# ProProject__20240517_2024-08-10.net
KiCad netlist of a schematic drawn in EasyEDA Pro
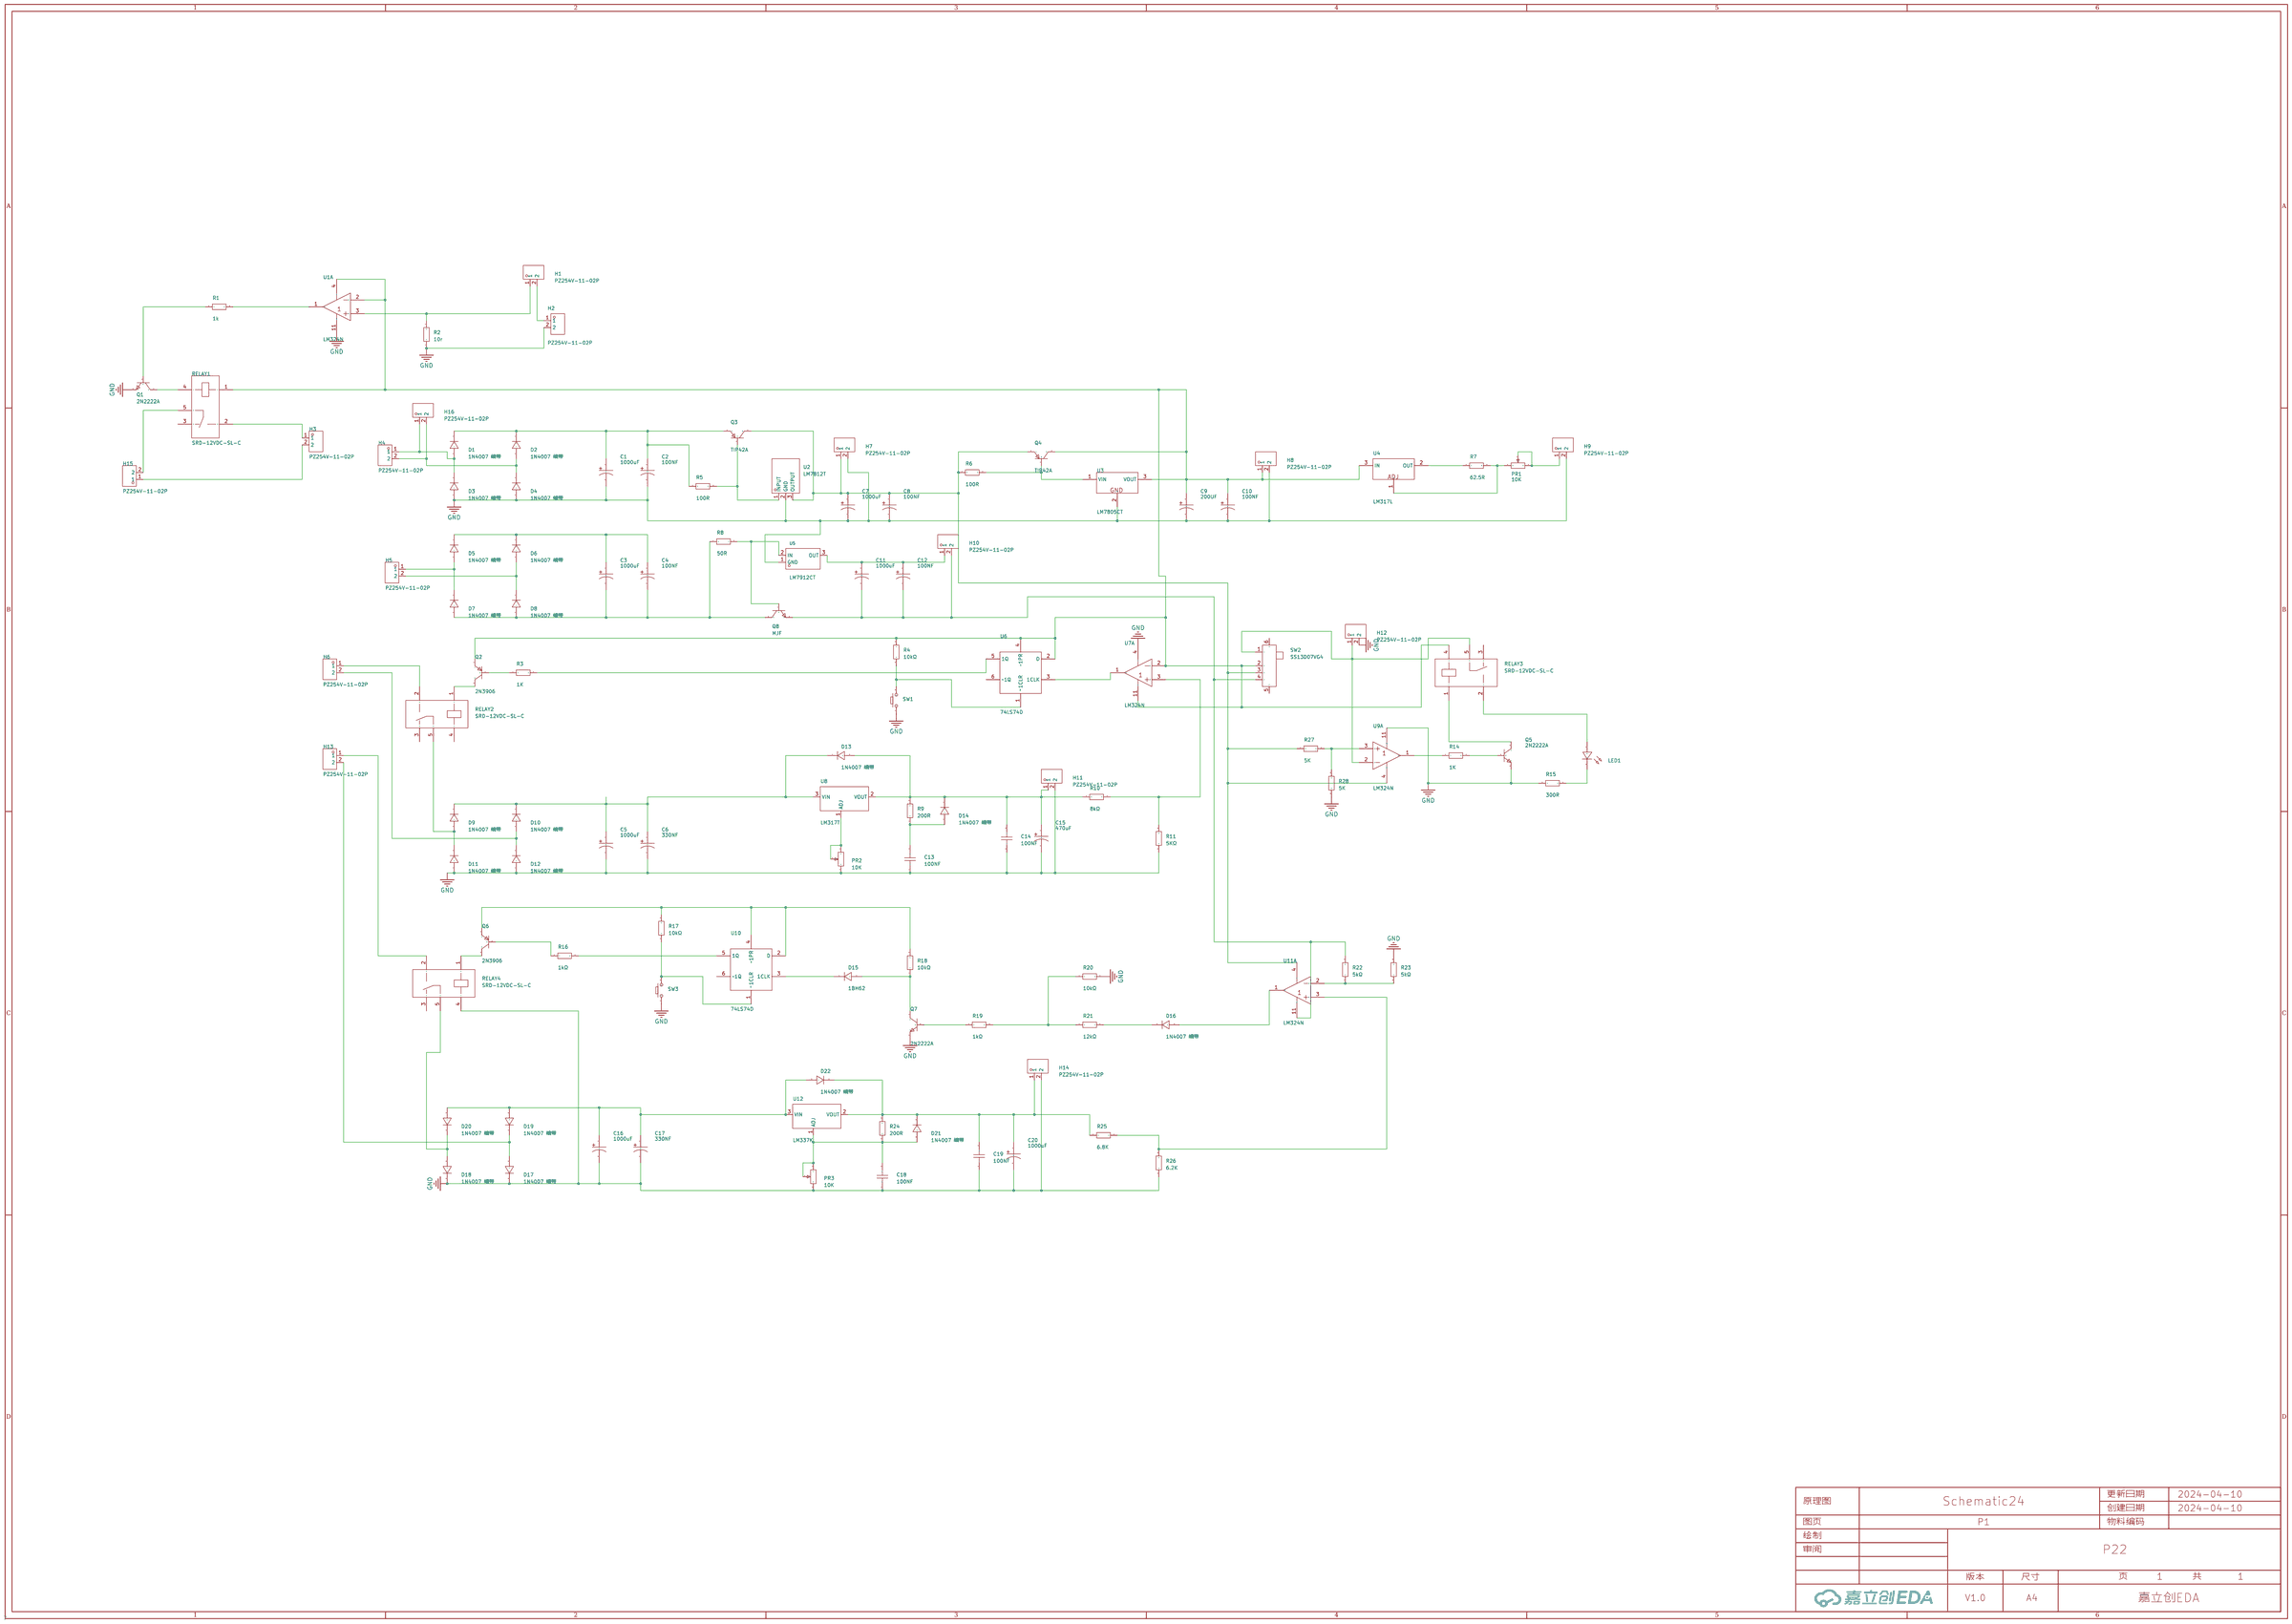
[diagram p0: schematic sheet]

(export (version "E")
  (design (tool "Eeschema 10.0.6"))
  (components
    (comp (ref "C1")
      (value "1000uF")
      (footprint "easyedapro:CAP-TH_BD12.5-P5.00-D0.6-FD")
      (description "容值:1000uF;精度:±20%;额定电压:35V;")
      (fields
        (field (name "Manufacturer Part") "ECLJ1321102M035P00")
        (field (name "Manufacturer") "TOPAZ(黄宝石)")
      )
      (libsource (lib "easyedapro") (part "ECLJ1321102M035P00"))
    )
    (comp (ref "C2")
      (value "100NF")
      (footprint "easyedapro:CAP-TH_BD12.5-P5.00-D0.6-FD")
      (description "容值:1000uF;精度:±20%;额定电压:35V;")
      (fields
        (field (name "Manufacturer Part") "ECLJ1321102M035P00")
        (field (name "Manufacturer") "TOPAZ(黄宝石)")
      )
      (libsource (lib "easyedapro") (part "ECLJ1321102M035P00"))
    )
    (comp (ref "C3")
      (value "1000uF")
      (footprint "easyedapro:CAP-TH_BD12.5-P5.00-D0.6-FD")
      (description "容值:1000uF;精度:±20%;额定电压:35V;")
      (fields
        (field (name "Manufacturer Part") "ECLJ1321102M035P00")
        (field (name "Manufacturer") "TOPAZ(黄宝石)")
      )
      (libsource (lib "easyedapro") (part "ECLJ1321102M035P00"))
    )
    (comp (ref "C4")
      (value "1000uF")
      (footprint "easyedapro:CAP-TH_BD12.5-P5.00-D0.6-FD")
      (description "容值:1000uF;精度:±20%;额定电压:35V;")
      (fields
        (field (name "Manufacturer Part") "ECLJ1321102M035P00")
        (field (name "Manufacturer") "TOPAZ(黄宝石)")
      )
      (libsource (lib "easyedapro") (part "ECLJ1321102M035P00"))
    )
    (comp (ref "C5")
      (value "1000uF")
      (footprint "easyedapro:CAP-TH_BD12.5-P5.00-D0.6-FD")
      (description "容值:1000uF;精度:±20%;额定电压:35V;")
      (fields
        (field (name "Manufacturer Part") "ECLJ1321102M035P00")
        (field (name "Manufacturer") "TOPAZ(黄宝石)")
      )
      (libsource (lib "easyedapro") (part "ECLJ1321102M035P00"))
    )
    (comp (ref "C6")
      (value "330NF")
      (footprint "easyedapro:CAP-TH_BD12.5-P5.00-D0.6-FD")
      (description "容值:1000uF;精度:±20%;额定电压:35V;")
      (fields
        (field (name "Manufacturer Part") "ECLJ1321102M035P00")
        (field (name "Manufacturer") "TOPAZ(黄宝石)")
      )
      (libsource (lib "easyedapro") (part "ECLJ1321102M035P00"))
    )
    (comp (ref "C7")
      (value "1000uF")
      (footprint "easyedapro:CAP-TH_BD12.5-P5.00-D0.6-FD")
      (description "容值:1000uF;精度:±20%;额定电压:35V;")
      (fields
        (field (name "Manufacturer Part") "ECLJ1321102M035P00")
        (field (name "Manufacturer") "TOPAZ(黄宝石)")
      )
      (libsource (lib "easyedapro") (part "ECLJ1321102M035P00"))
    )
    (comp (ref "C8")
      (value "100NF")
      (footprint "easyedapro:CAP-TH_BD12.5-P5.00-D0.6-FD")
      (description "容值:1000uF;精度:±20%;额定电压:35V;")
      (fields
        (field (name "Manufacturer Part") "ECLJ1321102M035P00")
        (field (name "Manufacturer") "TOPAZ(黄宝石)")
      )
      (libsource (lib "easyedapro") (part "ECLJ1321102M035P00"))
    )
    (comp (ref "C9")
      (value "200UF")
      (footprint "easyedapro:CAP-TH_BD12.5-P5.00-D0.6-FD")
      (description "容值:1000uF;精度:±20%;额定电压:35V;")
      (fields
        (field (name "Manufacturer Part") "ECLJ1321102M035P00")
        (field (name "Manufacturer") "TOPAZ(黄宝石)")
      )
      (libsource (lib "easyedapro") (part "ECLJ1321102M035P00"))
    )
    (comp (ref "C10")
      (value "100NF")
      (footprint "easyedapro:CAP-TH_BD12.5-P5.00-D0.6-FD")
      (description "容值:1000uF;精度:±20%;额定电压:35V;")
      (fields
        (field (name "Manufacturer Part") "ECLJ1321102M035P00")
        (field (name "Manufacturer") "TOPAZ(黄宝石)")
      )
      (libsource (lib "easyedapro") (part "ECLJ1321102M035P00"))
    )
    (comp (ref "C11")
      (value "1000uF")
      (footprint "easyedapro:CAP-TH_BD12.5-P5.00-D0.6-FD")
      (description "容值:1000uF;精度:±20%;额定电压:35V;")
      (fields
        (field (name "Manufacturer Part") "ECLJ1321102M035P00")
        (field (name "Manufacturer") "TOPAZ(黄宝石)")
      )
      (libsource (lib "easyedapro") (part "ECLJ1321102M035P00"))
    )
    (comp (ref "C12")
      (value "100NF")
      (footprint "easyedapro:CAP-TH_BD12.5-P5.00-D0.6-FD")
      (description "容值:1000uF;精度:±20%;额定电压:35V;")
      (fields
        (field (name "Manufacturer Part") "ECLJ1321102M035P00")
        (field (name "Manufacturer") "TOPAZ(黄宝石)")
      )
      (libsource (lib "easyedapro") (part "ECLJ1321102M035P00"))
    )
    (comp (ref "C13")
      (value "100NF")
      (footprint "easyedapro:CAP-TH_L5.5-W4.0-P5.00-D0.5")
      (description "容值:1nF;精度:±10%;额定电压:2kV;温度系数:SL;")
      (fields
        (field (name "Manufacturer Part") "Y5P102K2KV16CC0224")
        (field (name "Manufacturer") "KNSCHA(科尼盛)")
      )
      (libsource (lib "easyedapro") (part "Y5P102K2KV16CC0224"))
    )
    (comp (ref "C14")
      (value "100NF")
      (footprint "easyedapro:CAP-TH_L5.5-W4.0-P5.00-D0.5")
      (description "容值:1nF;精度:±10%;额定电压:2kV;温度系数:SL;")
      (fields
        (field (name "Manufacturer Part") "Y5P102K2KV16CC0224")
        (field (name "Manufacturer") "KNSCHA(科尼盛)")
      )
      (libsource (lib "easyedapro") (part "Y5P102K2KV16CC0224"))
    )
    (comp (ref "C15")
      (value "470uF")
      (footprint "easyedapro:CAP-TH_BD12.5-P5.00-D0.6-FD")
      (description "容值:1000uF;精度:±20%;额定电压:35V;")
      (fields
        (field (name "Manufacturer Part") "ECLJ1321102M035P00")
        (field (name "Manufacturer") "TOPAZ(黄宝石)")
      )
      (libsource (lib "easyedapro") (part "ECLJ1321102M035P00"))
    )
    (comp (ref "C16")
      (value "1000uF")
      (footprint "easyedapro:CAP-TH_BD12.5-P5.00-D0.6-FD")
      (description "容值:1000uF;精度:±20%;额定电压:35V;")
      (fields
        (field (name "Manufacturer Part") "ECLJ1321102M035P00")
        (field (name "Manufacturer") "TOPAZ(黄宝石)")
      )
      (libsource (lib "easyedapro") (part "ECLJ1321102M035P00"))
    )
    (comp (ref "C17")
      (value "330NF")
      (footprint "easyedapro:CAP-TH_BD12.5-P5.00-D0.6-FD")
      (description "容值:1000uF;精度:±20%;额定电压:35V;")
      (fields
        (field (name "Manufacturer Part") "ECLJ1321102M035P00")
        (field (name "Manufacturer") "TOPAZ(黄宝石)")
      )
      (libsource (lib "easyedapro") (part "ECLJ1321102M035P00"))
    )
    (comp (ref "C18")
      (value "100NF")
      (footprint "easyedapro:CAP-TH_L5.5-W4.0-P5.00-D0.5")
      (description "容值:1nF;精度:±10%;额定电压:2kV;温度系数:SL;")
      (fields
        (field (name "Manufacturer Part") "Y5P102K2KV16CC0224")
        (field (name "Manufacturer") "KNSCHA(科尼盛)")
      )
      (libsource (lib "easyedapro") (part "Y5P102K2KV16CC0224"))
    )
    (comp (ref "C19")
      (value "100NF")
      (footprint "easyedapro:CAP-TH_L5.5-W4.0-P5.00-D0.5")
      (description "容值:1nF;精度:±10%;额定电压:2kV;温度系数:SL;")
      (fields
        (field (name "Manufacturer Part") "Y5P102K2KV16CC0224")
        (field (name "Manufacturer") "KNSCHA(科尼盛)")
      )
      (libsource (lib "easyedapro") (part "Y5P102K2KV16CC0224"))
    )
    (comp (ref "C20")
      (value "1000uF")
      (footprint "easyedapro:CAP-TH_BD12.5-P5.00-D0.6-FD")
      (description "容值:1000uF;精度:±20%;额定电压:35V;")
      (fields
        (field (name "Manufacturer Part") "ECLJ1321102M035P00")
        (field (name "Manufacturer") "TOPAZ(黄宝石)")
      )
      (libsource (lib "easyedapro") (part "ECLJ1321102M035P00"))
    )
    (comp (ref "D1")
      (value "1N4007 编带")
      (footprint "easyedapro:DO-41_BD2.4-L4.7-P8.70-D0.9-RD")
      (description "二极管配置:-;正向压降(Vf):1.1V@1A;直流反向耐压(Vr):1kV;平均整流电流(Io):1A;")
      (fields (field (name "Manufacturer") "MDD"))
      (libsource (lib "easyedapro") (part "1N4007 Tube"))
    )
    (comp (ref "D2")
      (value "1N4007 编带")
      (footprint "easyedapro:DO-41_BD2.4-L4.7-P8.70-D0.9-RD")
      (description "二极管配置:-;正向压降(Vf):1.1V@1A;直流反向耐压(Vr):1kV;平均整流电流(Io):1A;")
      (fields (field (name "Manufacturer") "MDD"))
      (libsource (lib "easyedapro") (part "1N4007 Tube"))
    )
    (comp (ref "D3")
      (value "1N4007 编带")
      (footprint "easyedapro:DO-41_BD2.4-L4.7-P8.70-D0.9-RD")
      (description "二极管配置:-;正向压降(Vf):1.1V@1A;直流反向耐压(Vr):1kV;平均整流电流(Io):1A;")
      (fields (field (name "Manufacturer") "MDD"))
      (libsource (lib "easyedapro") (part "1N4007 Tube"))
    )
    (comp (ref "D4")
      (value "1N4007 编带")
      (footprint "easyedapro:DO-41_BD2.4-L4.7-P8.70-D0.9-RD")
      (description "二极管配置:-;正向压降(Vf):1.1V@1A;直流反向耐压(Vr):1kV;平均整流电流(Io):1A;")
      (fields (field (name "Manufacturer") "MDD"))
      (libsource (lib "easyedapro") (part "1N4007 Tube"))
    )
    (comp (ref "D5")
      (value "1N4007 编带")
      (footprint "easyedapro:DO-41_BD2.4-L4.7-P8.70-D0.9-RD")
      (description "二极管配置:-;正向压降(Vf):1.1V@1A;直流反向耐压(Vr):1kV;平均整流电流(Io):1A;")
      (fields (field (name "Manufacturer") "MDD"))
      (libsource (lib "easyedapro") (part "1N4007 Tube"))
    )
    (comp (ref "D6")
      (value "1N4007 编带")
      (footprint "easyedapro:DO-41_BD2.4-L4.7-P8.70-D0.9-RD")
      (description "二极管配置:-;正向压降(Vf):1.1V@1A;直流反向耐压(Vr):1kV;平均整流电流(Io):1A;")
      (fields (field (name "Manufacturer") "MDD"))
      (libsource (lib "easyedapro") (part "1N4007 Tube"))
    )
    (comp (ref "D7")
      (value "1N4007 编带")
      (footprint "easyedapro:DO-41_BD2.4-L4.7-P8.70-D0.9-RD")
      (description "二极管配置:-;正向压降(Vf):1.1V@1A;直流反向耐压(Vr):1kV;平均整流电流(Io):1A;")
      (fields (field (name "Manufacturer") "MDD"))
      (libsource (lib "easyedapro") (part "1N4007 Tube"))
    )
    (comp (ref "D8")
      (value "1N4007 编带")
      (footprint "easyedapro:DO-41_BD2.4-L4.7-P8.70-D0.9-RD")
      (description "二极管配置:-;正向压降(Vf):1.1V@1A;直流反向耐压(Vr):1kV;平均整流电流(Io):1A;")
      (fields (field (name "Manufacturer") "MDD"))
      (libsource (lib "easyedapro") (part "1N4007 Tube"))
    )
    (comp (ref "D9")
      (value "1N4007 编带")
      (footprint "easyedapro:DO-41_BD2.4-L4.7-P8.70-D0.9-RD")
      (description "二极管配置:-;正向压降(Vf):1.1V@1A;直流反向耐压(Vr):1kV;平均整流电流(Io):1A;")
      (fields (field (name "Manufacturer") "MDD"))
      (libsource (lib "easyedapro") (part "1N4007 Tube"))
    )
    (comp (ref "D10")
      (value "1N4007 编带")
      (footprint "easyedapro:DO-41_BD2.4-L4.7-P8.70-D0.9-RD")
      (description "二极管配置:-;正向压降(Vf):1.1V@1A;直流反向耐压(Vr):1kV;平均整流电流(Io):1A;")
      (fields (field (name "Manufacturer") "MDD"))
      (libsource (lib "easyedapro") (part "1N4007 Tube"))
    )
    (comp (ref "D11")
      (value "1N4007 编带")
      (footprint "easyedapro:DO-41_BD2.4-L4.7-P8.70-D0.9-RD")
      (description "二极管配置:-;正向压降(Vf):1.1V@1A;直流反向耐压(Vr):1kV;平均整流电流(Io):1A;")
      (fields (field (name "Manufacturer") "MDD"))
      (libsource (lib "easyedapro") (part "1N4007 Tube"))
    )
    (comp (ref "D12")
      (value "1N4007 编带")
      (footprint "easyedapro:DO-41_BD2.4-L4.7-P8.70-D0.9-RD")
      (description "二极管配置:-;正向压降(Vf):1.1V@1A;直流反向耐压(Vr):1kV;平均整流电流(Io):1A;")
      (fields (field (name "Manufacturer") "MDD"))
      (libsource (lib "easyedapro") (part "1N4007 Tube"))
    )
    (comp (ref "D13")
      (value "1N4007 编带")
      (footprint "easyedapro:DO-41_BD2.4-L4.7-P8.70-D0.9-RD")
      (description "二极管配置:-;正向压降(Vf):1.1V@1A;直流反向耐压(Vr):1kV;平均整流电流(Io):1A;")
      (fields (field (name "Manufacturer") "MDD"))
      (libsource (lib "easyedapro") (part "1N4007 Tube"))
    )
    (comp (ref "D14")
      (value "1N4007 编带")
      (footprint "easyedapro:DO-41_BD2.4-L4.7-P8.70-D0.9-RD")
      (description "二极管配置:-;正向压降(Vf):1.1V@1A;直流反向耐压(Vr):1kV;平均整流电流(Io):1A;")
      (fields (field (name "Manufacturer") "MDD"))
      (libsource (lib "easyedapro") (part "1N4007 Tube"))
    )
    (comp (ref "D15")
      (value "1BH62")
      (footprint "easyedapro:DO-41_BD2.4-L4.7-P8.70-D0.9-RD")
      (description "二极管配置:-;正向压降(Vf):1.1V@1A;直流反向耐压(Vr):1kV;平均整流电流(Io):1A;")
      (fields (field (name "Manufacturer") "MDD"))
      (libsource (lib "easyedapro") (part "1N4007 Tube"))
    )
    (comp (ref "D16")
      (value "1N4007 编带")
      (footprint "easyedapro:DO-41_BD2.4-L4.7-P8.70-D0.9-RD")
      (description "二极管配置:-;正向压降(Vf):1.1V@1A;直流反向耐压(Vr):1kV;平均整流电流(Io):1A;")
      (fields (field (name "Manufacturer") "MDD"))
      (libsource (lib "easyedapro") (part "1N4007 Tube"))
    )
    (comp (ref "D17")
      (value "1N4007 编带")
      (footprint "easyedapro:DO-41_BD2.4-L4.7-P8.70-D0.9-RD")
      (description "二极管配置:-;正向压降(Vf):1.1V@1A;直流反向耐压(Vr):1kV;平均整流电流(Io):1A;")
      (fields (field (name "Manufacturer") "MDD"))
      (libsource (lib "easyedapro") (part "1N4007 Tube"))
    )
    (comp (ref "D18")
      (value "1N4007 编带")
      (footprint "easyedapro:DO-41_BD2.4-L4.7-P8.70-D0.9-RD")
      (description "二极管配置:-;正向压降(Vf):1.1V@1A;直流反向耐压(Vr):1kV;平均整流电流(Io):1A;")
      (fields (field (name "Manufacturer") "MDD"))
      (libsource (lib "easyedapro") (part "1N4007 Tube"))
    )
    (comp (ref "D19")
      (value "1N4007 编带")
      (footprint "easyedapro:DO-41_BD2.4-L4.7-P8.70-D0.9-RD")
      (description "二极管配置:-;正向压降(Vf):1.1V@1A;直流反向耐压(Vr):1kV;平均整流电流(Io):1A;")
      (fields (field (name "Manufacturer") "MDD"))
      (libsource (lib "easyedapro") (part "1N4007 Tube"))
    )
    (comp (ref "D20")
      (value "1N4007 编带")
      (footprint "easyedapro:DO-41_BD2.4-L4.7-P8.70-D0.9-RD")
      (description "二极管配置:-;正向压降(Vf):1.1V@1A;直流反向耐压(Vr):1kV;平均整流电流(Io):1A;")
      (fields (field (name "Manufacturer") "MDD"))
      (libsource (lib "easyedapro") (part "1N4007 Tube"))
    )
    (comp (ref "D21")
      (value "1N4007 编带")
      (footprint "easyedapro:DO-41_BD2.4-L4.7-P8.70-D0.9-RD")
      (description "二极管配置:-;正向压降(Vf):1.1V@1A;直流反向耐压(Vr):1kV;平均整流电流(Io):1A;")
      (fields (field (name "Manufacturer") "MDD"))
      (libsource (lib "easyedapro") (part "1N4007 Tube"))
    )
    (comp (ref "D22")
      (value "1N4007 编带")
      (footprint "easyedapro:DO-41_BD2.4-L4.7-P8.70-D0.9-RD")
      (description "二极管配置:-;正向压降(Vf):1.1V@1A;直流反向耐压(Vr):1kV;平均整流电流(Io):1A;")
      (fields (field (name "Manufacturer") "MDD"))
      (libsource (lib "easyedapro") (part "1N4007 Tube"))
    )
    (comp (ref "H1")
      (value "PZ254V-11-02P")
      (footprint "easyedapro:HDR-TH_2P-P2.54-V-M")
      (fields (field (name "Manufacturer") "XFCN(兴飞)"))
      (libsource (lib "easyedapro") (part "PZ254V-11-02P"))
    )
    (comp (ref "H2")
      (value "PZ254V-11-02P")
      (footprint "easyedapro:HDR-TH_2P-P2.54-V-M")
      (fields (field (name "Manufacturer") "XFCN(兴飞)"))
      (libsource (lib "easyedapro") (part "PZ254V-11-02P"))
    )
    (comp (ref "H3")
      (value "PZ254V-11-02P")
      (footprint "easyedapro:HDR-TH_2P-P2.54-V-M")
      (fields (field (name "Manufacturer") "XFCN(兴飞)"))
      (libsource (lib "easyedapro") (part "PZ254V-11-02P"))
    )
    (comp (ref "H4")
      (value "PZ254V-11-02P")
      (footprint "easyedapro:HDR-TH_2P-P2.54-V-M")
      (fields (field (name "Manufacturer") "XFCN(兴飞)"))
      (libsource (lib "easyedapro") (part "PZ254V-11-02P"))
    )
    (comp (ref "H5")
      (value "PZ254V-11-02P")
      (footprint "easyedapro:HDR-TH_2P-P2.54-V-M")
      (fields (field (name "Manufacturer") "XFCN(兴飞)"))
      (libsource (lib "easyedapro") (part "PZ254V-11-02P"))
    )
    (comp (ref "H6")
      (value "PZ254V-11-02P")
      (footprint "easyedapro:HDR-TH_2P-P2.54-V-M")
      (fields (field (name "Manufacturer") "XFCN(兴飞)"))
      (libsource (lib "easyedapro") (part "PZ254V-11-02P"))
    )
    (comp (ref "H7")
      (value "PZ254V-11-02P")
      (footprint "easyedapro:HDR-TH_2P-P2.54-V-M")
      (fields (field (name "Manufacturer") "XFCN(兴飞)"))
      (libsource (lib "easyedapro") (part "PZ254V-11-02P"))
    )
    (comp (ref "H8")
      (value "PZ254V-11-02P")
      (footprint "easyedapro:HDR-TH_2P-P2.54-V-M")
      (fields (field (name "Manufacturer") "XFCN(兴飞)"))
      (libsource (lib "easyedapro") (part "PZ254V-11-02P"))
    )
    (comp (ref "H9")
      (value "PZ254V-11-02P")
      (footprint "easyedapro:HDR-TH_2P-P2.54-V-M")
      (fields (field (name "Manufacturer") "XFCN(兴飞)"))
      (libsource (lib "easyedapro") (part "PZ254V-11-02P"))
    )
    (comp (ref "H10")
      (value "PZ254V-11-02P")
      (footprint "easyedapro:HDR-TH_2P-P2.54-V-M")
      (fields (field (name "Manufacturer") "XFCN(兴飞)"))
      (libsource (lib "easyedapro") (part "PZ254V-11-02P"))
    )
    (comp (ref "H11")
      (value "PZ254V-11-02P")
      (footprint "easyedapro:HDR-TH_2P-P2.54-V-M")
      (fields (field (name "Manufacturer") "XFCN(兴飞)"))
      (libsource (lib "easyedapro") (part "PZ254V-11-02P"))
    )
    (comp (ref "H12")
      (value "PZ254V-11-02P")
      (footprint "easyedapro:HDR-TH_2P-P2.54-V-M")
      (fields (field (name "Manufacturer") "XFCN(兴飞)"))
      (libsource (lib "easyedapro") (part "PZ254V-11-02P"))
    )
    (comp (ref "H13")
      (value "PZ254V-11-02P")
      (footprint "easyedapro:HDR-TH_2P-P2.54-V-M")
      (fields (field (name "Manufacturer") "XFCN(兴飞)"))
      (libsource (lib "easyedapro") (part "PZ254V-11-02P"))
    )
    (comp (ref "H14")
      (value "PZ254V-11-02P")
      (footprint "easyedapro:HDR-TH_2P-P2.54-V-M")
      (fields (field (name "Manufacturer") "XFCN(兴飞)"))
      (libsource (lib "easyedapro") (part "PZ254V-11-02P"))
    )
    (comp (ref "H15")
      (value "PZ254V-11-02P")
      (footprint "easyedapro:HDR-TH_2P-P2.54-V-M")
      (fields (field (name "Manufacturer") "XFCN(兴飞)"))
      (libsource (lib "easyedapro") (part "PZ254V-11-02P"))
    )
    (comp (ref "H16")
      (value "PZ254V-11-02P")
      (footprint "easyedapro:HDR-TH_2P-P2.54-V-M")
      (fields (field (name "Manufacturer") "XFCN(兴飞)"))
      (libsource (lib "easyedapro") (part "PZ254V-11-02P"))
    )
    (comp (ref "LED1")
      (value "~")
      (footprint "easyedapro:LED_TH-3mm")
      (libsource (lib "easyedapro") (part "LED_TH-R"))
    )
    (comp (ref "PR1")
      (value "10K")
      (footprint "easyedapro:R_3386P")
      (libsource (lib "easyedapro") (part "3386P-1-103LF"))
    )
    (comp (ref "PR2")
      (value "10K")
      (footprint "easyedapro:R_3386P")
      (libsource (lib "easyedapro") (part "3386P-1-103LF"))
    )
    (comp (ref "PR3")
      (value "10K")
      (footprint "easyedapro:R_3386P")
      (libsource (lib "easyedapro") (part "3386P-1-103LF"))
    )
    (comp (ref "Q1")
      (value "2N2222A")
      (footprint "easyedapro:TO-92-3_L4.8-W3.7-P2.54-R")
      (description "晶体管类型:NPN;集电极电流(Ic):600mA;集射极击穿电压(Vceo):40V;功率(Pd):625mW;直流电流增益(hFE@Ic,Vce):100@150mA,10V;")
      (fields (field (name "Manufacturer") "BLUE ROCKET(蓝箭)"))
      (libsource (lib "easyedapro") (part "2N2222A"))
    )
    (comp (ref "Q2")
      (value "2N3906")
      (footprint "easyedapro:TO-92-3_L4.9-W3.7-P1.27-L")
      (description "晶体管类型:PNP;集电极电流(Ic):200mA;集射极击穿电压(Vceo):40V;功率(Pd):625mW;直流电流增益(hFE@Ic,Vce):100@10mA,1V;")
      (fields (field (name "Manufacturer") "JSMSEMI(杰盛微)"))
      (libsource (lib "easyedapro") (part "2N3906_C2874603"))
    )
    (comp (ref "Q3")
      (value "TIP42A")
      (footprint "easyedapro:TO-220-3_L10.2-W4.5-P2.54-L")
      (description "晶体管类型:PNP;集电极电流(Ic):6A;集射极击穿电压(Vceo):60V;功率(Pd):2W;直流电流增益(hFE@Ic,Vce):15@3A,4V;")
      (fields (field (name "Manufacturer") "ST(意法半导体)"))
      (libsource (lib "easyedapro") (part "TIP42A"))
    )
    (comp (ref "Q4")
      (value "TIP42A")
      (footprint "easyedapro:TO-220-3_L10.2-W4.5-P2.54-L")
      (description "晶体管类型:PNP;集电极电流(Ic):6A;集射极击穿电压(Vceo):60V;功率(Pd):2W;直流电流增益(hFE@Ic,Vce):15@3A,4V;")
      (fields (field (name "Manufacturer") "ST(意法半导体)"))
      (libsource (lib "easyedapro") (part "TIP42A"))
    )
    (comp (ref "Q5")
      (value "2N2222A")
      (footprint "easyedapro:TO-92-3_L4.8-W3.7-P2.54-R")
      (description "晶体管类型:NPN;集电极电流(Ic):600mA;集射极击穿电压(Vceo):40V;功率(Pd):625mW;直流电流增益(hFE@Ic,Vce):100@150mA,10V;")
      (fields (field (name "Manufacturer") "BLUE ROCKET(蓝箭)"))
      (libsource (lib "easyedapro") (part "2N2222A"))
    )
    (comp (ref "Q6")
      (value "2N3906")
      (footprint "easyedapro:TO-92-3_L4.9-W3.7-P1.27-L")
      (description "晶体管类型:PNP;集电极电流(Ic):200mA;集射极击穿电压(Vceo):40V;功率(Pd):625mW;直流电流增益(hFE@Ic,Vce):100@10mA,1V;")
      (fields (field (name "Manufacturer") "JSMSEMI(杰盛微)"))
      (libsource (lib "easyedapro") (part "2N3906_C2874603"))
    )
    (comp (ref "Q7")
      (value "2N2222A")
      (footprint "easyedapro:TO-92-3_L4.8-W3.7-P2.54-R")
      (description "晶体管类型:NPN;集电极电流(Ic):600mA;集射极击穿电压(Vceo):40V;功率(Pd):625mW;直流电流增益(hFE@Ic,Vce):100@150mA,10V;")
      (fields (field (name "Manufacturer") "BLUE ROCKET(蓝箭)"))
      (libsource (lib "easyedapro") (part "2N2222A"))
    )
    (comp (ref "Q8")
      (value "MJF")
      (footprint "easyedapro:TO-92-3_L4.8-W3.7-P2.54-R")
      (description "晶体管类型:NPN;集电极电流(Ic):600mA;集射极击穿电压(Vceo):40V;功率(Pd):625mW;直流电流增益(hFE@Ic,Vce):100@150mA,10V;")
      (fields (field (name "Manufacturer") "BLUE ROCKET(蓝箭)"))
      (libsource (lib "easyedapro") (part "2N2222A"))
    )
    (comp (ref "R1")
      (value "1k")
      (footprint "easyedapro:Res_1/8W")
      (libsource (lib "easyedapro") (part "电阻"))
    )
    (comp (ref "R2")
      (value "10r")
      (footprint "easyedapro:Res_1/8W")
      (libsource (lib "easyedapro") (part "电阻"))
    )
    (comp (ref "R3")
      (value "1K")
      (footprint "easyedapro:Res_1/8W")
      (libsource (lib "easyedapro") (part "电阻"))
    )
    (comp (ref "R4")
      (value "10kΩ")
      (footprint "easyedapro:Res_1/8W")
      (libsource (lib "easyedapro") (part "电阻"))
    )
    (comp (ref "R5")
      (value "100R")
      (footprint "easyedapro:Res_1/8W")
      (libsource (lib "easyedapro") (part "电阻"))
    )
    (comp (ref "R6")
      (value "100R")
      (footprint "easyedapro:Res_1/8W")
      (libsource (lib "easyedapro") (part "电阻"))
    )
    (comp (ref "R7")
      (value "62.5R")
      (footprint "easyedapro:Res_1/8W")
      (libsource (lib "easyedapro") (part "电阻"))
    )
    (comp (ref "R8")
      (value "50R")
      (footprint "easyedapro:Res_1/8W")
      (libsource (lib "easyedapro") (part "电阻"))
    )
    (comp (ref "R9")
      (value "200R")
      (footprint "easyedapro:Res_1/8W")
      (libsource (lib "easyedapro") (part "电阻"))
    )
    (comp (ref "R10")
      (value "8kΩ")
      (footprint "easyedapro:Res_1/8W")
      (libsource (lib "easyedapro") (part "电阻"))
    )
    (comp (ref "R11")
      (value "5KΩ")
      (footprint "easyedapro:Res_1/8W")
      (libsource (lib "easyedapro") (part "电阻"))
    )
    (comp (ref "R14")
      (value "1K")
      (footprint "easyedapro:Res_1/8W")
      (libsource (lib "easyedapro") (part "电阻"))
    )
    (comp (ref "R15")
      (value "300R")
      (footprint "easyedapro:Res_1/8W")
      (libsource (lib "easyedapro") (part "电阻"))
    )
    (comp (ref "R16")
      (value "1kΩ")
      (footprint "easyedapro:Res_1/8W")
      (libsource (lib "easyedapro") (part "电阻"))
    )
    (comp (ref "R17")
      (value "10kΩ")
      (footprint "easyedapro:Res_1/8W")
      (libsource (lib "easyedapro") (part "电阻"))
    )
    (comp (ref "R18")
      (value "10kΩ")
      (footprint "easyedapro:Res_1/8W")
      (libsource (lib "easyedapro") (part "电阻"))
    )
    (comp (ref "R19")
      (value "1kΩ")
      (footprint "easyedapro:Res_1/8W")
      (libsource (lib "easyedapro") (part "电阻"))
    )
    (comp (ref "R20")
      (value "10kΩ")
      (footprint "easyedapro:Res_1/8W")
      (libsource (lib "easyedapro") (part "电阻"))
    )
    (comp (ref "R21")
      (value "12kΩ")
      (footprint "easyedapro:Res_1/8W")
      (libsource (lib "easyedapro") (part "电阻"))
    )
    (comp (ref "R22")
      (value "5kΩ")
      (footprint "easyedapro:Res_1/8W")
      (libsource (lib "easyedapro") (part "电阻"))
    )
    (comp (ref "R23")
      (value "5kΩ")
      (footprint "easyedapro:Res_1/8W")
      (libsource (lib "easyedapro") (part "电阻"))
    )
    (comp (ref "R24")
      (value "200R")
      (footprint "easyedapro:Res_1/8W")
      (libsource (lib "easyedapro") (part "电阻"))
    )
    (comp (ref "R25")
      (value "6.8K")
      (footprint "easyedapro:Res_1/8W")
      (libsource (lib "easyedapro") (part "电阻"))
    )
    (comp (ref "R26")
      (value "6.2K")
      (footprint "easyedapro:Res_1/8W")
      (libsource (lib "easyedapro") (part "电阻"))
    )
    (comp (ref "R27")
      (value "5K")
      (footprint "easyedapro:Res_1/8W")
      (libsource (lib "easyedapro") (part "电阻"))
    )
    (comp (ref "R28")
      (value "5K")
      (footprint "easyedapro:Res_1/8W")
      (libsource (lib "easyedapro") (part "电阻"))
    )
    (comp (ref "RELAY1")
      (value "SRD-12VDC-SL-C")
      (footprint "easyedapro:RELAY-TH_SRD-XXVDC-XL-C")
      (description "线圈电压:12V;触点形式:一组转换:1C(单刀双掷-转换);触点容量(电阻负载):-;最大切换电压:250V@AC;最大切换电流:15A;")
      (fields (field (name "Manufacturer") "松乐"))
      (libsource (lib "easyedapro") (part "SRD-12VDC-SL-C"))
    )
    (comp (ref "RELAY2")
      (value "SRD-12VDC-SL-C")
      (footprint "easyedapro:RELAY-TH_SRD-XXVDC-XL-C")
      (description "线圈电压:12V;触点形式:一组转换:1C(单刀双掷-转换);触点容量(电阻负载):-;最大切换电压:250V@AC;最大切换电流:15A;")
      (fields (field (name "Manufacturer") "松乐"))
      (libsource (lib "easyedapro") (part "SRD-12VDC-SL-C"))
    )
    (comp (ref "RELAY3")
      (value "SRD-12VDC-SL-C")
      (footprint "easyedapro:RELAY-TH_SRD-XXVDC-XL-C")
      (description "线圈电压:12V;触点形式:一组转换:1C(单刀双掷-转换);触点容量(电阻负载):-;最大切换电压:250V@AC;最大切换电流:15A;")
      (fields (field (name "Manufacturer") "松乐"))
      (libsource (lib "easyedapro") (part "SRD-12VDC-SL-C"))
    )
    (comp (ref "RELAY4")
      (value "SRD-12VDC-SL-C")
      (footprint "easyedapro:RELAY-TH_SRD-XXVDC-XL-C")
      (description "线圈电压:12V;触点形式:一组转换:1C(单刀双掷-转换);触点容量(电阻负载):-;最大切换电压:250V@AC;最大切换电流:15A;")
      (fields (field (name "Manufacturer") "松乐"))
      (libsource (lib "easyedapro") (part "SRD-12VDC-SL-C"))
    )
    (comp (ref "SW1")
      (value "~")
      (footprint "easyedapro:Key_TH_3.5x6x4.3")
      (libsource (lib "easyedapro") (part "Key_TH_3.5x6x4.3"))
    )
    (comp (ref "SW2")
      (value "SS13D07VG4")
      (footprint "easyedapro:SW-TH_SS13D07VG4")
      (description "电路结构:单刀三掷;安装方式:直插;开关颜色:-;额定电流(DC):500mA;额定电压(DC):50V;额定电流(AC):-;额定电压(AC):-;机械寿命:5千次;")
      (fields (field (name "Manufacturer") "SHOU HAN(首韩)"))
      (libsource (lib "easyedapro") (part "SS13D07VG4"))
    )
    (comp (ref "SW3")
      (value "~")
      (footprint "easyedapro:Key_TH_3.5x6x4.3")
      (libsource (lib "easyedapro") (part "Key_TH_3.5x6x4.3"))
    )
    (comp (ref "U1")
      (value "LM324N")
      (footprint "easyedapro:DIP-14_L19.4-W6.4-P2.54-LS7.6-BL")
      (description "放大器数:-;")
      (fields (field (name "Manufacturer") "HGSEMI(华冠)"))
      (libsource (lib "easyedapro") (part "LM324N_C725320"))
    )
    (comp (ref "U2")
      (value "LM7812T")
      (footprint "easyedapro:TO-220-3_L10.0-W4.5-P2.54-L")
      (fields (field (name "Manufacturer") "HGSEMI(华冠)"))
      (libsource (lib "easyedapro") (part "LM7812T"))
    )
    (comp (ref "U3")
      (value "LM7805CT")
      (footprint "easyedapro:TO-220-3_L10.2-W4.6-P2.54-L")
      (description "输出类型:固定;最大输入电压:35V;输出电压:5V;最大输出电流:1.5A;输出极性:正极;")
      (fields (field (name "Manufacturer") "Siproin(上海矽朋)"))
      (libsource (lib "easyedapro") (part "LM7805CT_C5444281"))
    )
    (comp (ref "U4")
      (value "LM317L")
      (footprint "easyedapro:TO-92-3_L4.9-W3.7-P1.27-L")
      (description "输出类型:可调;最大输入电压:40V;输出电压:1.2V~37V;最大输出电流:100mA;输出极性:正极;")
      (fields (field (name "Manufacturer") "HTC"))
      (libsource (lib "easyedapro") (part "LM317L"))
    )
    (comp (ref "U5")
      (value "LM7912CT")
      (footprint "easyedapro:TO-220-3_L10.0-W4.6-P2.54-L")
      (description "线性稳压器(LDO) 1.5A版本")
      (fields (field (name "Manufacturer") "HGSEMI(华冠)"))
      (libsource (lib "easyedapro") (part "LM7912CT_C7432211"))
    )
    (comp (ref "U6") (value "74LS74D") (libsource (lib "easyedapro") (part "74LS74D")))
    (comp (ref "U7")
      (value "LM324N")
      (footprint "easyedapro:DIP-14_L19.4-W6.4-P2.54-LS7.6-BL")
      (description "放大器数:-;")
      (fields (field (name "Manufacturer") "HGSEMI(华冠)"))
      (libsource (lib "easyedapro") (part "LM324N_C725320"))
    )
    (comp (ref "U8")
      (value "LM317T")
      (footprint "easyedapro:TO-220-3_L10.0-W4.6-P2.54-L")
      (description "输出类型:可调;最大输入电压:40V;输出电压:1.7V~37V;最大输出电流:1.5A;输出极性:正极;")
      (fields (field (name "Manufacturer") "Siproin(上海矽朋)"))
      (libsource (lib "easyedapro") (part "LM317T_C5444279"))
    )
    (comp (ref "U9")
      (value "LM324N")
      (footprint "easyedapro:DIP-14_L19.4-W6.4-P2.54-LS7.6-BL")
      (description "放大器数:-;")
      (fields (field (name "Manufacturer") "HGSEMI(华冠)"))
      (libsource (lib "easyedapro") (part "LM324N_C725320"))
    )
    (comp (ref "U10") (value "74LS74D") (libsource (lib "easyedapro") (part "74LS74D")))
    (comp (ref "U11")
      (value "LM324N")
      (footprint "easyedapro:DIP-14_L19.4-W6.4-P2.54-LS7.6-BL")
      (description "放大器数:-;")
      (fields (field (name "Manufacturer") "HGSEMI(华冠)"))
      (libsource (lib "easyedapro") (part "LM324N_C725320"))
    )
    (comp (ref "U12")
      (value "LM337K")
      (footprint "easyedapro:TO-220-3_L10.0-W4.6-P2.54-L")
      (description "输出类型:可调;最大输入电压:40V;输出电压:1.7V~37V;最大输出电流:1.5A;输出极性:正极;")
      (fields (field (name "Manufacturer") "Siproin(上海矽朋)"))
      (libsource (lib "easyedapro") (part "LM317T_C5444279"))
    )
  )
  (nets
    (net (code "1") (name "GND") (class "Default")
      (node (ref "C1") (pin "2") (pinfunction "2_2") (pintype "unspecified"))
      (node (ref "C10") (pin "2") (pinfunction "2_2") (pintype "unspecified"))
      (node (ref "C13") (pin "1") (pinfunction "1_1") (pintype "unspecified"))
      (node (ref "C14") (pin "1") (pinfunction "1_1") (pintype "unspecified"))
      (node (ref "C15") (pin "2") (pinfunction "2_2") (pintype "unspecified"))
      (node (ref "C16") (pin "2") (pinfunction "2_2") (pintype "unspecified"))
      (node (ref "C17") (pin "2") (pinfunction "2_2") (pintype "unspecified"))
      (node (ref "C18") (pin "1") (pinfunction "1_1") (pintype "unspecified"))
      (node (ref "C19") (pin "1") (pinfunction "1_1") (pintype "unspecified"))
      (node (ref "C2") (pin "2") (pinfunction "2_2") (pintype "unspecified"))
      (node (ref "C20") (pin "2") (pinfunction "2_2") (pintype "unspecified"))
      (node (ref "C5") (pin "2") (pinfunction "2_2") (pintype "unspecified"))
      (node (ref "C6") (pin "2") (pinfunction "2_2") (pintype "unspecified"))
      (node (ref "C7") (pin "2") (pinfunction "2_2") (pintype "unspecified"))
      (node (ref "C8") (pin "2") (pinfunction "2_2") (pintype "unspecified"))
      (node (ref "C9") (pin "2") (pinfunction "2_2") (pintype "unspecified"))
      (node (ref "D11") (pin "2") (pinfunction "A_2") (pintype "unspecified"))
      (node (ref "D12") (pin "2") (pinfunction "A_2") (pintype "unspecified"))
      (node (ref "D17") (pin "1") (pinfunction "K_1") (pintype "unspecified"))
      (node (ref "D18") (pin "1") (pinfunction "K_1") (pintype "unspecified"))
      (node (ref "D3") (pin "2") (pinfunction "A_2") (pintype "unspecified"))
      (node (ref "D4") (pin "2") (pinfunction "A_2") (pintype "unspecified"))
      (node (ref "H11") (pin "2") (pinfunction "2_2") (pintype "unspecified"))
      (node (ref "H12") (pin "2") (pinfunction "2_2") (pintype "unspecified"))
      (node (ref "H14") (pin "2") (pinfunction "2_2") (pintype "unspecified"))
      (node (ref "H2") (pin "2") (pinfunction "2_2") (pintype "unspecified"))
      (node (ref "H7") (pin "2") (pinfunction "2_2") (pintype "unspecified"))
      (node (ref "H8") (pin "2") (pinfunction "2_2") (pintype "unspecified"))
      (node (ref "H9") (pin "2") (pinfunction "2_2") (pintype "unspecified"))
      (node (ref "PR2") (pin "3") (pinfunction "3_3") (pintype "input"))
      (node (ref "PR3") (pin "3") (pinfunction "3_3") (pintype "input"))
      (node (ref "Q1") (pin "3") (pinfunction "E_3") (pintype "unspecified"))
      (node (ref "Q5") (pin "3") (pinfunction "E_3") (pintype "unspecified"))
      (node (ref "Q7") (pin "3") (pinfunction "E_3") (pintype "unspecified"))
      (node (ref "R11") (pin "1") (pinfunction "1_1") (pintype "input"))
      (node (ref "R15") (pin "1") (pinfunction "1_1") (pintype "input"))
      (node (ref "R2") (pin "1") (pinfunction "1_1") (pintype "input"))
      (node (ref "R20") (pin "2") (pinfunction "2_2") (pintype "input"))
      (node (ref "R23") (pin "2") (pinfunction "2_2") (pintype "input"))
      (node (ref "R26") (pin "1") (pinfunction "1_1") (pintype "input"))
      (node (ref "R28") (pin "1") (pinfunction "1_1") (pintype "input"))
      (node (ref "RELAY4") (pin "4") (pinfunction "4_4") (pintype "input"))
      (node (ref "SW1") (pin "A") (pinfunction "A_A") (pintype "input"))
      (node (ref "SW3") (pin "A") (pinfunction "A_A") (pintype "input"))
      (node (ref "U1") (pin "11") (pinfunction "GND_11") (pintype "unspecified"))
      (node (ref "U2") (pin "2") (pinfunction "GND_2") (pintype "unspecified"))
      (node (ref "U3") (pin "2") (pinfunction "GND_2") (pintype "unspecified"))
      (node (ref "U5") (pin "1") (pinfunction "GND_1") (pintype "input"))
      (node (ref "U7") (pin "4") (pinfunction "VCC_4") (pintype "unspecified"))
      (node (ref "U9") (pin "11") (pinfunction "GND_11") (pintype "unspecified"))
    )
    (net (code "2") (name "Net-(D1-A)") (class "Default")
      (node (ref "D1") (pin "2") (pinfunction "A_2") (pintype "unspecified"))
      (node (ref "D3") (pin "1") (pinfunction "K_1") (pintype "unspecified"))
      (node (ref "H16") (pin "1") (pinfunction "1_1") (pintype "unspecified"))
      (node (ref "H4") (pin "1") (pinfunction "1_1") (pintype "unspecified"))
    )
    (net (code "3") (name "Net-(D1-K)") (class "Default")
      (node (ref "C1") (pin "1") (pinfunction "1_1") (pintype "unspecified"))
      (node (ref "C2") (pin "1") (pinfunction "1_1") (pintype "unspecified"))
      (node (ref "D1") (pin "1") (pinfunction "K_1") (pintype "unspecified"))
      (node (ref "D2") (pin "1") (pinfunction "K_1") (pintype "unspecified"))
      (node (ref "Q3") (pin "3") (pinfunction "E_3") (pintype "input"))
      (node (ref "R5") (pin "1") (pinfunction "1_1") (pintype "input"))
    )
    (net (code "4") (name "Net-(D2-A)") (class "Default")
      (node (ref "D2") (pin "2") (pinfunction "A_2") (pintype "unspecified"))
      (node (ref "D4") (pin "1") (pinfunction "K_1") (pintype "unspecified"))
      (node (ref "H16") (pin "2") (pinfunction "2_2") (pintype "unspecified"))
      (node (ref "H4") (pin "2") (pinfunction "2_2") (pintype "unspecified"))
    )
    (net (code "5") (name "Net-(D5-A)") (class "Default")
      (node (ref "D5") (pin "2") (pinfunction "A_2") (pintype "unspecified"))
      (node (ref "D7") (pin "1") (pinfunction "K_1") (pintype "unspecified"))
      (node (ref "H5") (pin "1") (pinfunction "1_1") (pintype "unspecified"))
    )
    (net (code "6") (name "Net-(D5-K)") (class "Default")
      (node (ref "C3") (pin "1") (pinfunction "1_1") (pintype "unspecified"))
      (node (ref "C4") (pin "1") (pinfunction "1_1") (pintype "unspecified"))
      (node (ref "D5") (pin "1") (pinfunction "K_1") (pintype "unspecified"))
      (node (ref "D6") (pin "1") (pinfunction "K_1") (pintype "unspecified"))
    )
    (net (code "7") (name "Net-(D6-A)") (class "Default")
      (node (ref "D6") (pin "2") (pinfunction "A_2") (pintype "unspecified"))
      (node (ref "D8") (pin "1") (pinfunction "K_1") (pintype "unspecified"))
      (node (ref "H5") (pin "2") (pinfunction "2_2") (pintype "unspecified"))
    )
    (net (code "8") (name "Net-(D7-A)") (class "Default")
      (node (ref "C3") (pin "2") (pinfunction "2_2") (pintype "unspecified"))
      (node (ref "C4") (pin "2") (pinfunction "2_2") (pintype "unspecified"))
      (node (ref "D7") (pin "2") (pinfunction "A_2") (pintype "unspecified"))
      (node (ref "D8") (pin "2") (pinfunction "A_2") (pintype "unspecified"))
      (node (ref "Q8") (pin "1") (pinfunction "C_1") (pintype "unspecified"))
      (node (ref "R8") (pin "1") (pinfunction "1_1") (pintype "input"))
    )
    (net (code "9") (name "Net-(D10-A)") (class "Default")
      (node (ref "D10") (pin "2") (pinfunction "A_2") (pintype "unspecified"))
      (node (ref "D12") (pin "1") (pinfunction "K_1") (pintype "unspecified"))
      (node (ref "H6") (pin "2") (pinfunction "2_2") (pintype "unspecified"))
    )
    (net (code "10") (name "Net-(D10-K)") (class "Default")
      (node (ref "C5") (pin "1") (pinfunction "1_1") (pintype "unspecified"))
      (node (ref "C6") (pin "1") (pinfunction "1_1") (pintype "unspecified"))
      (node (ref "D10") (pin "1") (pinfunction "K_1") (pintype "unspecified"))
      (node (ref "D13") (pin "1") (pinfunction "K_1") (pintype "unspecified"))
      (node (ref "D9") (pin "1") (pinfunction "K_1") (pintype "unspecified"))
      (node (ref "U8") (pin "3") (pinfunction "VIN_3") (pintype "unspecified"))
    )
    (net (code "11") (name "Net-(D11-K)") (class "Default")
      (node (ref "D11") (pin "1") (pinfunction "K_1") (pintype "unspecified"))
      (node (ref "D9") (pin "2") (pinfunction "A_2") (pintype "unspecified"))
      (node (ref "RELAY2") (pin "5") (pinfunction "5_5") (pintype "input"))
    )
    (net (code "12") (name "Net-(D13-A)") (class "Default")
      (node (ref "C14") (pin "2") (pinfunction "2_2") (pintype "unspecified"))
      (node (ref "C15") (pin "1") (pinfunction "1_1") (pintype "unspecified"))
      (node (ref "D13") (pin "2") (pinfunction "A_2") (pintype "unspecified"))
      (node (ref "D14") (pin "1") (pinfunction "K_1") (pintype "unspecified"))
      (node (ref "H11") (pin "1") (pinfunction "1_1") (pintype "unspecified"))
      (node (ref "R10") (pin "1") (pinfunction "1_1") (pintype "input"))
      (node (ref "R9") (pin "2") (pinfunction "2_2") (pintype "input"))
      (node (ref "U8") (pin "2") (pinfunction "VOUT_2") (pintype "unspecified"))
    )
    (net (code "13") (name "Net-(D14-A)") (class "Default")
      (node (ref "C13") (pin "2") (pinfunction "2_2") (pintype "unspecified"))
      (node (ref "D14") (pin "2") (pinfunction "A_2") (pintype "unspecified"))
      (node (ref "R9") (pin "1") (pinfunction "1_1") (pintype "input"))
    )
    (net (code "14") (name "Net-(D15-A)") (class "Default")
      (node (ref "D15") (pin "2") (pinfunction "A_2") (pintype "unspecified"))
      (node (ref "Q7") (pin "1") (pinfunction "C_1") (pintype "unspecified"))
      (node (ref "R18") (pin "1") (pinfunction "1_1") (pintype "input"))
    )
    (net (code "15") (name "Net-(D15-K)") (class "Default")
      (node (ref "D15") (pin "1") (pinfunction "K_1") (pintype "unspecified"))
      (node (ref "U10") (pin "3") (pinfunction "1CLK_3") (pintype "input"))
    )
    (net (code "16") (name "Net-(D16-A)") (class "Default")
      (node (ref "D16") (pin "2") (pinfunction "A_2") (pintype "unspecified"))
      (node (ref "U11") (pin "1") (pinfunction "OUT1_1") (pintype "output"))
    )
    (net (code "17") (name "Net-(D16-K)") (class "Default")
      (node (ref "D16") (pin "1") (pinfunction "K_1") (pintype "unspecified"))
      (node (ref "R21") (pin "2") (pinfunction "2_2") (pintype "input"))
    )
    (net (code "18") (name "Net-(D17-A)") (class "Default")
      (node (ref "D17") (pin "2") (pinfunction "A_2") (pintype "unspecified"))
      (node (ref "D19") (pin "1") (pinfunction "K_1") (pintype "unspecified"))
      (node (ref "H13") (pin "2") (pinfunction "2_2") (pintype "unspecified"))
    )
    (net (code "19") (name "Net-(D18-A)") (class "Default")
      (node (ref "D18") (pin "2") (pinfunction "A_2") (pintype "unspecified"))
      (node (ref "D20") (pin "1") (pinfunction "K_1") (pintype "unspecified"))
      (node (ref "RELAY4") (pin "5") (pinfunction "5_5") (pintype "input"))
    )
    (net (code "20") (name "Net-(D19-A)") (class "Default")
      (node (ref "C16") (pin "1") (pinfunction "1_1") (pintype "unspecified"))
      (node (ref "C17") (pin "1") (pinfunction "1_1") (pintype "unspecified"))
      (node (ref "D19") (pin "2") (pinfunction "A_2") (pintype "unspecified"))
      (node (ref "D20") (pin "2") (pinfunction "A_2") (pintype "unspecified"))
      (node (ref "D22") (pin "2") (pinfunction "A_2") (pintype "unspecified"))
      (node (ref "U12") (pin "3") (pinfunction "VIN_3") (pintype "unspecified"))
    )
    (net (code "21") (name "Net-(D21-A)") (class "Default")
      (node (ref "C18") (pin "2") (pinfunction "2_2") (pintype "unspecified"))
      (node (ref "D21") (pin "2") (pinfunction "A_2") (pintype "unspecified"))
      (node (ref "PR3") (pin "1") (pinfunction "1_1") (pintype "input"))
      (node (ref "PR3") (pin "2") (pinfunction "2_2") (pintype "input"))
      (node (ref "R24") (pin "1") (pinfunction "1_1") (pintype "input"))
      (node (ref "U12") (pin "1") (pinfunction "ADJ_1") (pintype "unspecified"))
    )
    (net (code "22") (name "Net-(D21-K)") (class "Default")
      (node (ref "C19") (pin "2") (pinfunction "2_2") (pintype "unspecified"))
      (node (ref "C20") (pin "1") (pinfunction "1_1") (pintype "unspecified"))
      (node (ref "D21") (pin "1") (pinfunction "K_1") (pintype "unspecified"))
      (node (ref "D22") (pin "1") (pinfunction "K_1") (pintype "unspecified"))
      (node (ref "H14") (pin "1") (pinfunction "1_1") (pintype "unspecified"))
      (node (ref "R24") (pin "2") (pinfunction "2_2") (pintype "input"))
      (node (ref "R25") (pin "1") (pinfunction "1_1") (pintype "input"))
      (node (ref "U12") (pin "2") (pinfunction "VOUT_2") (pintype "unspecified"))
    )
    (net (code "23") (name "Net-(H1-Pad2)") (class "Default")
      (node (ref "H1") (pin "2") (pinfunction "2_2") (pintype "unspecified"))
      (node (ref "H2") (pin "1") (pinfunction "1_1") (pintype "unspecified"))
    )
    (net (code "24") (name "Net-(H3-Pad1)") (class "Default")
      (node (ref "H3") (pin "1") (pinfunction "1_1") (pintype "unspecified"))
      (node (ref "RELAY1") (pin "2") (pinfunction "2_2") (pintype "input"))
    )
    (net (code "25") (name "Net-(H6-Pad1)") (class "Default")
      (node (ref "H6") (pin "1") (pinfunction "1_1") (pintype "unspecified"))
      (node (ref "RELAY2") (pin "2") (pinfunction "2_2") (pintype "input"))
    )
    (net (code "26") (name "Net-(H9-Pad1)") (class "Default")
      (node (ref "H9") (pin "1") (pinfunction "1_1") (pintype "unspecified"))
      (node (ref "PR1") (pin "1") (pinfunction "1_1") (pintype "input"))
      (node (ref "PR1") (pin "2") (pinfunction "2_2") (pintype "input"))
    )
    (net (code "27") (name "Net-(H13-Pad1)") (class "Default")
      (node (ref "H13") (pin "1") (pinfunction "1_1") (pintype "unspecified"))
      (node (ref "RELAY4") (pin "2") (pinfunction "2_2") (pintype "input"))
    )
    (net (code "28") (name "Net-(H15-Pad1)") (class "Default")
      (node (ref "H15") (pin "1") (pinfunction "1_1") (pintype "unspecified"))
      (node (ref "H3") (pin "2") (pinfunction "2_2") (pintype "unspecified"))
    )
    (net (code "29") (name "Net-(H15-Pad2)") (class "Default")
      (node (ref "H15") (pin "2") (pinfunction "2_2") (pintype "unspecified"))
      (node (ref "RELAY1") (pin "5") (pinfunction "5_5") (pintype "input"))
    )
    (net (code "30") (name "Net-(LED1-A)") (class "Default")
      (node (ref "LED1") (pin "2") (pinfunction "A_2") (pintype "input"))
      (node (ref "R15") (pin "2") (pinfunction "2_2") (pintype "input"))
    )
    (net (code "31") (name "Net-(LED1-C)") (class "Default")
      (node (ref "LED1") (pin "1") (pinfunction "C_1") (pintype "input"))
      (node (ref "RELAY3") (pin "2") (pinfunction "2_2") (pintype "input"))
    )
    (net (code "32") (name "Net-(Q1-B)") (class "Default")
      (node (ref "Q1") (pin "2") (pinfunction "B_2") (pintype "unspecified"))
      (node (ref "R1") (pin "1") (pinfunction "1_1") (pintype "input"))
    )
    (net (code "33") (name "Net-(Q1-C)") (class "Default")
      (node (ref "Q1") (pin "1") (pinfunction "C_1") (pintype "unspecified"))
      (node (ref "RELAY1") (pin "4") (pinfunction "4_4") (pintype "input"))
    )
    (net (code "34") (name "Net-(Q2-B)") (class "Default")
      (node (ref "Q2") (pin "2") (pinfunction "B_2") (pintype "unspecified"))
      (node (ref "R3") (pin "1") (pinfunction "1_1") (pintype "input"))
    )
    (net (code "35") (name "Net-(Q2-C)") (class "Default")
      (node (ref "Q2") (pin "3") (pinfunction "C_3") (pintype "unspecified"))
      (node (ref "RELAY2") (pin "1") (pinfunction "1_1") (pintype "input"))
    )
    (net (code "36") (name "Net-(Q2-E)") (class "Default")
      (node (ref "C10") (pin "1") (pinfunction "1_1") (pintype "unspecified"))
      (node (ref "C9") (pin "1") (pinfunction "1_1") (pintype "unspecified"))
      (node (ref "H8") (pin "1") (pinfunction "1_1") (pintype "unspecified"))
      (node (ref "Q2") (pin "1") (pinfunction "E_1") (pintype "unspecified"))
      (node (ref "Q4") (pin "2") (pinfunction "C_2") (pintype "input"))
      (node (ref "R4") (pin "2") (pinfunction "2_2") (pintype "input"))
      (node (ref "RELAY1") (pin "1") (pinfunction "1_1") (pintype "input"))
      (node (ref "RELAY3") (pin "4") (pinfunction "4_4") (pintype "input"))
      (node (ref "SW2") (pin "2") (pinfunction "2_2") (pintype "unspecified"))
      (node (ref "U1") (pin "2") (pinfunction "IN1-_2") (pintype "unspecified"))
      (node (ref "U1") (pin "4") (pinfunction "VCC_4") (pintype "unspecified"))
      (node (ref "U3") (pin "3") (pinfunction "VOUT_3") (pintype "unspecified"))
      (node (ref "U4") (pin "3") (pinfunction "IN_3") (pintype "input"))
      (node (ref "U6") (pin "2") (pinfunction "D_2") (pintype "input"))
      (node (ref "U6") (pin "4") (pinfunction "~1PR_4") (pintype "input"))
      (node (ref "U7") (pin "11") (pinfunction "GND_11") (pintype "unspecified"))
      (node (ref "U7") (pin "2") (pinfunction "IN1-_2") (pintype "unspecified"))
    )
    (net (code "37") (name "Net-(Q3-B)") (class "Default")
      (node (ref "Q3") (pin "1") (pinfunction "B_1") (pintype "input"))
      (node (ref "R5") (pin "2") (pinfunction "2_2") (pintype "input"))
      (node (ref "U2") (pin "1") (pinfunction "INPUT_1") (pintype "unspecified"))
    )
    (net (code "38") (name "Net-(Q3-C)") (class "Default")
      (node (ref "C7") (pin "1") (pinfunction "1_1") (pintype "unspecified"))
      (node (ref "C8") (pin "1") (pinfunction "1_1") (pintype "unspecified"))
      (node (ref "H7") (pin "1") (pinfunction "1_1") (pintype "unspecified"))
      (node (ref "Q3") (pin "2") (pinfunction "C_2") (pintype "input"))
      (node (ref "Q4") (pin "3") (pinfunction "E_3") (pintype "input"))
      (node (ref "R27") (pin "1") (pinfunction "1_1") (pintype "input"))
      (node (ref "R6") (pin "1") (pinfunction "1_1") (pintype "input"))
      (node (ref "SW2") (pin "3") (pinfunction "3_3") (pintype "unspecified"))
      (node (ref "U11") (pin "4") (pinfunction "VCC_4") (pintype "unspecified"))
      (node (ref "U2") (pin "3") (pinfunction "OUTPUT_3") (pintype "unspecified"))
      (node (ref "U9") (pin "4") (pinfunction "VCC_4") (pintype "unspecified"))
    )
    (net (code "39") (name "Net-(Q4-B)") (class "Default")
      (node (ref "Q4") (pin "1") (pinfunction "B_1") (pintype "input"))
      (node (ref "R6") (pin "2") (pinfunction "2_2") (pintype "input"))
      (node (ref "U3") (pin "1") (pinfunction "VIN_1") (pintype "unspecified"))
    )
    (net (code "40") (name "Net-(Q5-B)") (class "Default")
      (node (ref "Q5") (pin "2") (pinfunction "B_2") (pintype "unspecified"))
      (node (ref "R14") (pin "2") (pinfunction "2_2") (pintype "input"))
    )
    (net (code "41") (name "Net-(Q5-C)") (class "Default")
      (node (ref "Q5") (pin "1") (pinfunction "C_1") (pintype "unspecified"))
      (node (ref "RELAY3") (pin "1") (pinfunction "1_1") (pintype "input"))
    )
    (net (code "42") (name "Net-(Q6-B)") (class "Default")
      (node (ref "Q6") (pin "2") (pinfunction "B_2") (pintype "unspecified"))
      (node (ref "R16") (pin "1") (pinfunction "1_1") (pintype "input"))
    )
    (net (code "43") (name "Net-(Q6-C)") (class "Default")
      (node (ref "Q6") (pin "3") (pinfunction "C_3") (pintype "unspecified"))
      (node (ref "RELAY4") (pin "1") (pinfunction "1_1") (pintype "input"))
    )
    (net (code "44") (name "Net-(Q6-E)") (class "Default")
      (node (ref "Q6") (pin "1") (pinfunction "E_1") (pintype "unspecified"))
      (node (ref "R17") (pin "2") (pinfunction "2_2") (pintype "input"))
      (node (ref "R18") (pin "2") (pinfunction "2_2") (pintype "input"))
      (node (ref "U10") (pin "2") (pinfunction "D_2") (pintype "input"))
      (node (ref "U10") (pin "4") (pinfunction "~1PR_4") (pintype "input"))
    )
    (net (code "45") (name "Net-(Q7-B)") (class "Default")
      (node (ref "Q7") (pin "2") (pinfunction "B_2") (pintype "unspecified"))
      (node (ref "R19") (pin "1") (pinfunction "1_1") (pintype "input"))
    )
    (net (code "46") (name "Net-(Q8-B)") (class "Default")
      (node (ref "Q8") (pin "2") (pinfunction "B_2") (pintype "unspecified"))
      (node (ref "R8") (pin "2") (pinfunction "2_2") (pintype "input"))
      (node (ref "U5") (pin "2") (pinfunction "IN_2") (pintype "input"))
    )
    (net (code "47") (name "Net-(Q8-E)") (class "Default")
      (node (ref "C11") (pin "2") (pinfunction "2_2") (pintype "unspecified"))
      (node (ref "C12") (pin "2") (pinfunction "2_2") (pintype "unspecified"))
      (node (ref "H10") (pin "2") (pinfunction "2_2") (pintype "unspecified"))
      (node (ref "Q8") (pin "3") (pinfunction "E_3") (pintype "unspecified"))
      (node (ref "R22") (pin "2") (pinfunction "2_2") (pintype "input"))
      (node (ref "SW2") (pin "4") (pinfunction "4_4") (pintype "unspecified"))
      (node (ref "U11") (pin "11") (pinfunction "GND_11") (pintype "unspecified"))
    )
    (net (code "48") (name "Net-(R19-Pad2)") (class "Default")
      (node (ref "R19") (pin "2") (pinfunction "2_2") (pintype "input"))
      (node (ref "R20") (pin "1") (pinfunction "1_1") (pintype "input"))
      (node (ref "R21") (pin "1") (pinfunction "1_1") (pintype "input"))
    )
    (net (code "49") (name "Net-(U1A-IN1+)") (class "Default")
      (node (ref "H1") (pin "1") (pinfunction "1_1") (pintype "unspecified"))
      (node (ref "R2") (pin "2") (pinfunction "2_2") (pintype "input"))
      (node (ref "U1") (pin "3") (pinfunction "IN1+_3") (pintype "unspecified"))
    )
    (net (code "50") (name "Net-(U1A-OUT1)") (class "Default")
      (node (ref "R1") (pin "2") (pinfunction "2_2") (pintype "input"))
      (node (ref "U1") (pin "1") (pinfunction "OUT1_1") (pintype "output"))
    )
    (net (code "51") (name "Net-(U4-ADJ)") (class "Default")
      (node (ref "PR1") (pin "3") (pinfunction "3_3") (pintype "input"))
      (node (ref "R7") (pin "2") (pinfunction "2_2") (pintype "input"))
      (node (ref "U4") (pin "1") (pinfunction "ADJ_1") (pintype "input"))
    )
    (net (code "52") (name "Net-(U4-OUT)") (class "Default")
      (node (ref "R7") (pin "1") (pinfunction "1_1") (pintype "input"))
      (node (ref "U4") (pin "2") (pinfunction "OUT_2") (pintype "input"))
    )
    (net (code "53") (name "Net-(U5-OUT)") (class "Default")
      (node (ref "C11") (pin "1") (pinfunction "1_1") (pintype "unspecified"))
      (node (ref "C12") (pin "1") (pinfunction "1_1") (pintype "unspecified"))
      (node (ref "H10") (pin "1") (pinfunction "1_1") (pintype "unspecified"))
      (node (ref "U5") (pin "3") (pinfunction "OUT_3") (pintype "input"))
    )
    (net (code "54") (name "Net-(U6-1CLK)") (class "Default")
      (node (ref "U6") (pin "3") (pinfunction "1CLK_3") (pintype "input"))
      (node (ref "U7") (pin "1") (pinfunction "OUT1_1") (pintype "output"))
    )
    (net (code "55") (name "Net-(U6-1Q)") (class "Default")
      (node (ref "R3") (pin "2") (pinfunction "2_2") (pintype "input"))
      (node (ref "U6") (pin "5") (pinfunction "1Q_5") (pintype "output"))
    )
    (net (code "56") (name "Net-(U6-～1CLR)") (class "Default")
      (node (ref "R4") (pin "1") (pinfunction "1_1") (pintype "input"))
      (node (ref "SW1") (pin "B") (pinfunction "B_B") (pintype "input"))
      (node (ref "U6") (pin "1") (pinfunction "～1CLR_1") (pintype "input"))
    )
    (net (code "57") (name "Net-(U7A-IN1+)") (class "Default")
      (node (ref "R10") (pin "2") (pinfunction "2_2") (pintype "input"))
      (node (ref "R11") (pin "2") (pinfunction "2_2") (pintype "input"))
      (node (ref "U7") (pin "3") (pinfunction "IN1+_3") (pintype "unspecified"))
    )
    (net (code "58") (name "Net-(U8-ADJ)") (class "Default")
      (node (ref "PR2") (pin "1") (pinfunction "1_1") (pintype "input"))
      (node (ref "PR2") (pin "2") (pinfunction "2_2") (pintype "input"))
      (node (ref "U8") (pin "1") (pinfunction "ADJ_1") (pintype "unspecified"))
    )
    (net (code "59") (name "Net-(U9A-IN1+)") (class "Default")
      (node (ref "R27") (pin "2") (pinfunction "2_2") (pintype "input"))
      (node (ref "R28") (pin "2") (pinfunction "2_2") (pintype "input"))
      (node (ref "U9") (pin "3") (pinfunction "IN1+_3") (pintype "unspecified"))
    )
    (net (code "60") (name "Net-(U9A-IN1-)") (class "Default")
      (node (ref "H12") (pin "1") (pinfunction "1_1") (pintype "unspecified"))
      (node (ref "RELAY3") (pin "5") (pinfunction "5_5") (pintype "input"))
      (node (ref "SW2") (pin "1") (pinfunction "1_1") (pintype "unspecified"))
      (node (ref "U9") (pin "2") (pinfunction "IN1-_2") (pintype "unspecified"))
    )
    (net (code "61") (name "Net-(U9A-OUT1)") (class "Default")
      (node (ref "R14") (pin "1") (pinfunction "1_1") (pintype "input"))
      (node (ref "U9") (pin "1") (pinfunction "OUT1_1") (pintype "output"))
    )
    (net (code "62") (name "Net-(U10-1Q)") (class "Default")
      (node (ref "R16") (pin "2") (pinfunction "2_2") (pintype "input"))
      (node (ref "U10") (pin "5") (pinfunction "1Q_5") (pintype "output"))
    )
    (net (code "63") (name "Net-(U10-～1CLR)") (class "Default")
      (node (ref "R17") (pin "1") (pinfunction "1_1") (pintype "input"))
      (node (ref "SW3") (pin "B") (pinfunction "B_B") (pintype "input"))
      (node (ref "U10") (pin "1") (pinfunction "～1CLR_1") (pintype "input"))
    )
    (net (code "64") (name "Net-(U11A-IN1+)") (class "Default")
      (node (ref "R25") (pin "2") (pinfunction "2_2") (pintype "input"))
      (node (ref "R26") (pin "2") (pinfunction "2_2") (pintype "input"))
      (node (ref "U11") (pin "3") (pinfunction "IN1+_3") (pintype "unspecified"))
    )
    (net (code "65") (name "Net-(U11A-IN1-)") (class "Default")
      (node (ref "R22") (pin "1") (pinfunction "1_1") (pintype "input"))
      (node (ref "R23") (pin "1") (pinfunction "1_1") (pintype "input"))
      (node (ref "U11") (pin "2") (pinfunction "IN1-_2") (pintype "unspecified"))
    )
    (net (code "66") (name "unconnected-(RELAY1-Pad3)") (class "Default")
      (node (ref "RELAY1") (pin "3") (pinfunction "3_3") (pintype "input"))
    )
    (net (code "67") (name "unconnected-(RELAY2-Pad3)") (class "Default")
      (node (ref "RELAY2") (pin "3") (pinfunction "3_3") (pintype "input"))
    )
    (net (code "68") (name "unconnected-(RELAY2-Pad4)") (class "Default")
      (node (ref "RELAY2") (pin "4") (pinfunction "4_4") (pintype "input"))
    )
    (net (code "69") (name "unconnected-(RELAY3-Pad3)") (class "Default")
      (node (ref "RELAY3") (pin "3") (pinfunction "3_3") (pintype "input"))
    )
    (net (code "70") (name "unconnected-(RELAY4-Pad3)") (class "Default")
      (node (ref "RELAY4") (pin "3") (pinfunction "3_3") (pintype "input"))
    )
    (net (code "71") (name "unconnected-(SW2-Pad5)") (class "Default")
      (node (ref "SW2") (pin "5") (pinfunction "5_5") (pintype "unspecified"))
    )
    (net (code "72") (name "unconnected-(SW2-Pad6)") (class "Default")
      (node (ref "SW2") (pin "6") (pinfunction "6_6") (pintype "unspecified"))
    )
    (net (code "73") (name "unconnected-(U6-~1Q-Pad6)") (class "Default")
      (node (ref "U6") (pin "6") (pinfunction "~1Q_6") (pintype "output"))
    )
    (net (code "74") (name "unconnected-(U10-~1Q-Pad6)") (class "Default")
      (node (ref "U10") (pin "6") (pinfunction "~1Q_6") (pintype "output"))
    )
  )
)
